# coms.net
KiCad netlist of a schematic drawn in EAGLE
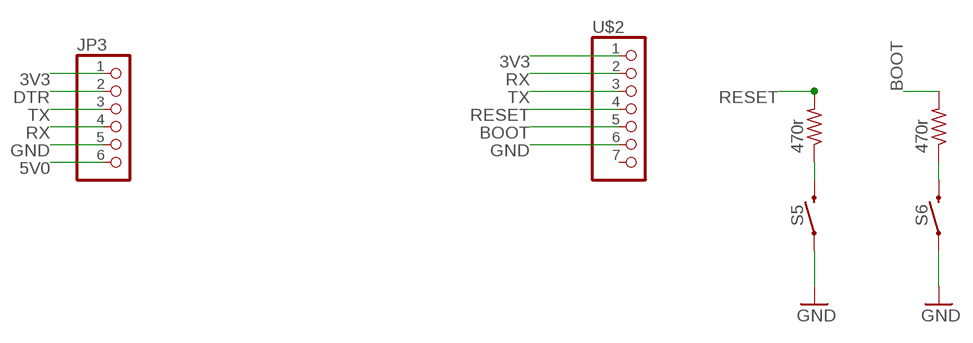
[diagram p0: schematic, sheet 1]
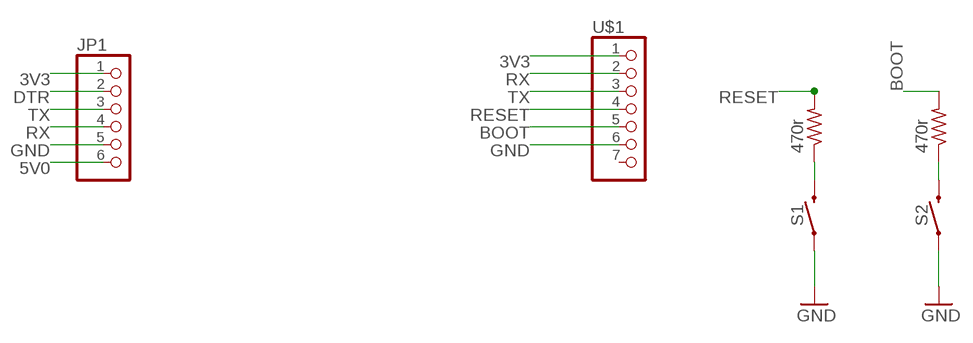
[diagram p1: schematic, sheet 2]
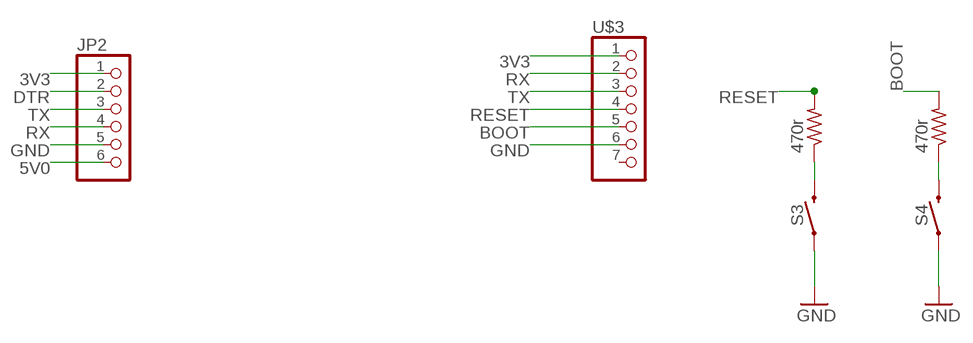
[diagram p2: schematic, sheet 3]

(export (version "E")
  (design (tool "Eeschema 10.0.6"))
  (components
    (comp (ref "JP1")
      (value "HEADER-1X6ROUND")
      (footprint "eagle-import:1X06_ROUND")
      (libsource (lib "eagle-import") (part "HEADER-1X6ROUND"))
    )
    (comp (ref "R1")
      (value "470r")
      (footprint "eagle-import:M1206")
      (libsource (lib "eagle-import") (part "R-US_M1206"))
    )
    (comp (ref "R2")
      (value "470r")
      (footprint "eagle-import:M1206")
      (libsource (lib "eagle-import") (part "R-US_M1206"))
    )
    (comp (ref "S1")
      (value "MOMENTARY-SWITCH-SPST")
      (footprint "eagle-import:TACTILE_SWITCH_C480275")
      (libsource (lib "eagle-import") (part "MOMENTARY-SWITCH-SPST"))
    )
    (comp (ref "S2")
      (value "MOMENTARY-SWITCH-SPST")
      (footprint "eagle-import:TACTILE_SWITCH_C480275")
      (libsource (lib "eagle-import") (part "MOMENTARY-SWITCH-SPST"))
    )
    (comp (ref "U$1")
      (value "HEADER-1X7ROUND")
      (footprint "eagle-import:1X07_ROUND")
      (libsource (lib "eagle-import") (part "HEADER-1X7ROUND"))
    )
    (comp (ref "JP3")
      (value "HEADER-1X6ROUND")
      (footprint "eagle-import:1X06_ROUND")
      (libsource (lib "eagle-import") (part "HEADER-1X6ROUND"))
    )
    (comp (ref "R5")
      (value "470r")
      (footprint "eagle-import:M1206")
      (libsource (lib "eagle-import") (part "R-US_M1206"))
    )
    (comp (ref "R6")
      (value "470r")
      (footprint "eagle-import:M1206")
      (libsource (lib "eagle-import") (part "R-US_M1206"))
    )
    (comp (ref "S5")
      (value "MOMENTARY-SWITCH-SPST")
      (footprint "eagle-import:TACTILE_SWITCH_C480275")
      (libsource (lib "eagle-import") (part "MOMENTARY-SWITCH-SPST"))
    )
    (comp (ref "S6")
      (value "MOMENTARY-SWITCH-SPST")
      (footprint "eagle-import:TACTILE_SWITCH_C480275")
      (libsource (lib "eagle-import") (part "MOMENTARY-SWITCH-SPST"))
    )
    (comp (ref "U$2")
      (value "HEADER-1X7ROUND")
      (footprint "eagle-import:1X07_ROUND")
      (libsource (lib "eagle-import") (part "HEADER-1X7ROUND"))
    )
    (comp (ref "JP2")
      (value "HEADER-1X6ROUND")
      (footprint "eagle-import:1X06_ROUND")
      (libsource (lib "eagle-import") (part "HEADER-1X6ROUND"))
    )
    (comp (ref "R3")
      (value "470r")
      (footprint "eagle-import:M1206")
      (libsource (lib "eagle-import") (part "R-US_M1206"))
    )
    (comp (ref "R4")
      (value "470r")
      (footprint "eagle-import:M1206")
      (libsource (lib "eagle-import") (part "R-US_M1206"))
    )
    (comp (ref "S3")
      (value "MOMENTARY-SWITCH-SPST")
      (footprint "eagle-import:TACTILE_SWITCH_C480275")
      (libsource (lib "eagle-import") (part "MOMENTARY-SWITCH-SPST"))
    )
    (comp (ref "S4")
      (value "MOMENTARY-SWITCH-SPST")
      (footprint "eagle-import:TACTILE_SWITCH_C480275")
      (libsource (lib "eagle-import") (part "MOMENTARY-SWITCH-SPST"))
    )
    (comp (ref "U$3")
      (value "HEADER-1X7ROUND")
      (footprint "eagle-import:1X07_ROUND")
      (libsource (lib "eagle-import") (part "HEADER-1X7ROUND"))
    )
  )
  (nets
    (net (code "1") (name "3V3") (class "Default")
      (node (ref "JP1") (pin "1") (pinfunction "1_1") (pintype "passive"))
      (node (ref "JP2") (pin "1") (pinfunction "1_1") (pintype "passive"))
      (node (ref "JP3") (pin "1") (pinfunction "1_1") (pintype "passive"))
      (node (ref "U$1") (pin "1") (pinfunction "1_1") (pintype "passive"))
      (node (ref "U$2") (pin "1") (pinfunction "1_1") (pintype "passive"))
      (node (ref "U$3") (pin "1") (pinfunction "1_1") (pintype "passive"))
    )
    (net (code "2") (name "5V0") (class "Default")
      (node (ref "JP1") (pin "6") (pinfunction "6_6") (pintype "passive"))
      (node (ref "JP2") (pin "6") (pinfunction "6_6") (pintype "passive"))
      (node (ref "JP3") (pin "6") (pinfunction "6_6") (pintype "passive"))
    )
    (net (code "3") (name "BOOT") (class "Default")
      (node (ref "R2") (pin "2") (pinfunction "2_2") (pintype "passive"))
      (node (ref "R4") (pin "2") (pinfunction "2_2") (pintype "passive"))
      (node (ref "R6") (pin "2") (pinfunction "2_2") (pintype "passive"))
      (node (ref "U$1") (pin "5") (pinfunction "5_5") (pintype "passive"))
      (node (ref "U$2") (pin "5") (pinfunction "5_5") (pintype "passive"))
      (node (ref "U$3") (pin "5") (pinfunction "5_5") (pintype "passive"))
    )
    (net (code "4") (name "DTR") (class "Default")
      (node (ref "JP1") (pin "2") (pinfunction "2_2") (pintype "passive"))
      (node (ref "JP2") (pin "2") (pinfunction "2_2") (pintype "passive"))
      (node (ref "JP3") (pin "2") (pinfunction "2_2") (pintype "passive"))
    )
    (net (code "5") (name "GND") (class "Default")
      (node (ref "JP1") (pin "5") (pinfunction "5_5") (pintype "passive"))
      (node (ref "JP2") (pin "5") (pinfunction "5_5") (pintype "passive"))
      (node (ref "JP3") (pin "5") (pinfunction "5_5") (pintype "passive"))
      (node (ref "S1") (pin "1") (pinfunction "1_1") (pintype "passive"))
      (node (ref "S1") (pin "2") (pinfunction "1_2") (pintype "passive"))
      (node (ref "S2") (pin "1") (pinfunction "1_1") (pintype "passive"))
      (node (ref "S2") (pin "2") (pinfunction "1_2") (pintype "passive"))
      (node (ref "S3") (pin "1") (pinfunction "1_1") (pintype "passive"))
      (node (ref "S3") (pin "2") (pinfunction "1_2") (pintype "passive"))
      (node (ref "S4") (pin "1") (pinfunction "1_1") (pintype "passive"))
      (node (ref "S4") (pin "2") (pinfunction "1_2") (pintype "passive"))
      (node (ref "S5") (pin "1") (pinfunction "1_1") (pintype "passive"))
      (node (ref "S5") (pin "2") (pinfunction "1_2") (pintype "passive"))
      (node (ref "S6") (pin "1") (pinfunction "1_1") (pintype "passive"))
      (node (ref "S6") (pin "2") (pinfunction "1_2") (pintype "passive"))
      (node (ref "U$1") (pin "6") (pinfunction "6_6") (pintype "passive"))
      (node (ref "U$2") (pin "6") (pinfunction "6_6") (pintype "passive"))
      (node (ref "U$3") (pin "6") (pinfunction "6_6") (pintype "passive"))
    )
    (net (code "6") (name "Net-(R1-Pad1)") (class "Default")
      (node (ref "R1") (pin "1") (pinfunction "1_1") (pintype "passive"))
      (node (ref "S1") (pin "3") (pinfunction "2_3") (pintype "passive"))
      (node (ref "S1") (pin "4") (pinfunction "2_4") (pintype "passive"))
    )
    (net (code "7") (name "Net-(R2-Pad1)") (class "Default")
      (node (ref "R2") (pin "1") (pinfunction "1_1") (pintype "passive"))
      (node (ref "S2") (pin "3") (pinfunction "2_3") (pintype "passive"))
      (node (ref "S2") (pin "4") (pinfunction "2_4") (pintype "passive"))
    )
    (net (code "8") (name "Net-(R3-Pad1)") (class "Default")
      (node (ref "R3") (pin "1") (pinfunction "1_1") (pintype "passive"))
      (node (ref "S3") (pin "3") (pinfunction "2_3") (pintype "passive"))
      (node (ref "S3") (pin "4") (pinfunction "2_4") (pintype "passive"))
    )
    (net (code "9") (name "Net-(R4-Pad1)") (class "Default")
      (node (ref "R4") (pin "1") (pinfunction "1_1") (pintype "passive"))
      (node (ref "S4") (pin "3") (pinfunction "2_3") (pintype "passive"))
      (node (ref "S4") (pin "4") (pinfunction "2_4") (pintype "passive"))
    )
    (net (code "10") (name "Net-(R5-Pad1)") (class "Default")
      (node (ref "R5") (pin "1") (pinfunction "1_1") (pintype "passive"))
      (node (ref "S5") (pin "3") (pinfunction "2_3") (pintype "passive"))
      (node (ref "S5") (pin "4") (pinfunction "2_4") (pintype "passive"))
    )
    (net (code "11") (name "Net-(R6-Pad1)") (class "Default")
      (node (ref "R6") (pin "1") (pinfunction "1_1") (pintype "passive"))
      (node (ref "S6") (pin "3") (pinfunction "2_3") (pintype "passive"))
      (node (ref "S6") (pin "4") (pinfunction "2_4") (pintype "passive"))
    )
    (net (code "12") (name "RESET") (class "Default")
      (node (ref "R1") (pin "2") (pinfunction "2_2") (pintype "passive"))
      (node (ref "R3") (pin "2") (pinfunction "2_2") (pintype "passive"))
      (node (ref "R5") (pin "2") (pinfunction "2_2") (pintype "passive"))
      (node (ref "U$1") (pin "4") (pinfunction "4_4") (pintype "passive"))
      (node (ref "U$2") (pin "4") (pinfunction "4_4") (pintype "passive"))
      (node (ref "U$3") (pin "4") (pinfunction "4_4") (pintype "passive"))
    )
    (net (code "13") (name "RX") (class "Default")
      (node (ref "JP1") (pin "4") (pinfunction "4_4") (pintype "passive"))
      (node (ref "JP2") (pin "4") (pinfunction "4_4") (pintype "passive"))
      (node (ref "JP3") (pin "4") (pinfunction "4_4") (pintype "passive"))
      (node (ref "U$1") (pin "2") (pinfunction "2_2") (pintype "passive"))
      (node (ref "U$2") (pin "2") (pinfunction "2_2") (pintype "passive"))
      (node (ref "U$3") (pin "2") (pinfunction "2_2") (pintype "passive"))
    )
    (net (code "14") (name "TX") (class "Default")
      (node (ref "JP1") (pin "3") (pinfunction "3_3") (pintype "passive"))
      (node (ref "JP2") (pin "3") (pinfunction "3_3") (pintype "passive"))
      (node (ref "JP3") (pin "3") (pinfunction "3_3") (pintype "passive"))
      (node (ref "U$1") (pin "3") (pinfunction "3_3") (pintype "passive"))
      (node (ref "U$2") (pin "3") (pinfunction "3_3") (pintype "passive"))
      (node (ref "U$3") (pin "3") (pinfunction "3_3") (pintype "passive"))
    )
    (net (code "15") (name "unconnected-(U$1-Pad7)") (class "Default")
      (node (ref "U$1") (pin "7") (pinfunction "7_7") (pintype "passive"))
    )
    (net (code "16") (name "unconnected-(U$2-Pad7)") (class "Default")
      (node (ref "U$2") (pin "7") (pinfunction "7_7") (pintype "passive"))
    )
    (net (code "17") (name "unconnected-(U$3-Pad7)") (class "Default")
      (node (ref "U$3") (pin "7") (pinfunction "7_7") (pintype "passive"))
    )
  )
)
